# stm32_rf_pio.net
KiCad netlist of a schematic drawn in EAGLE
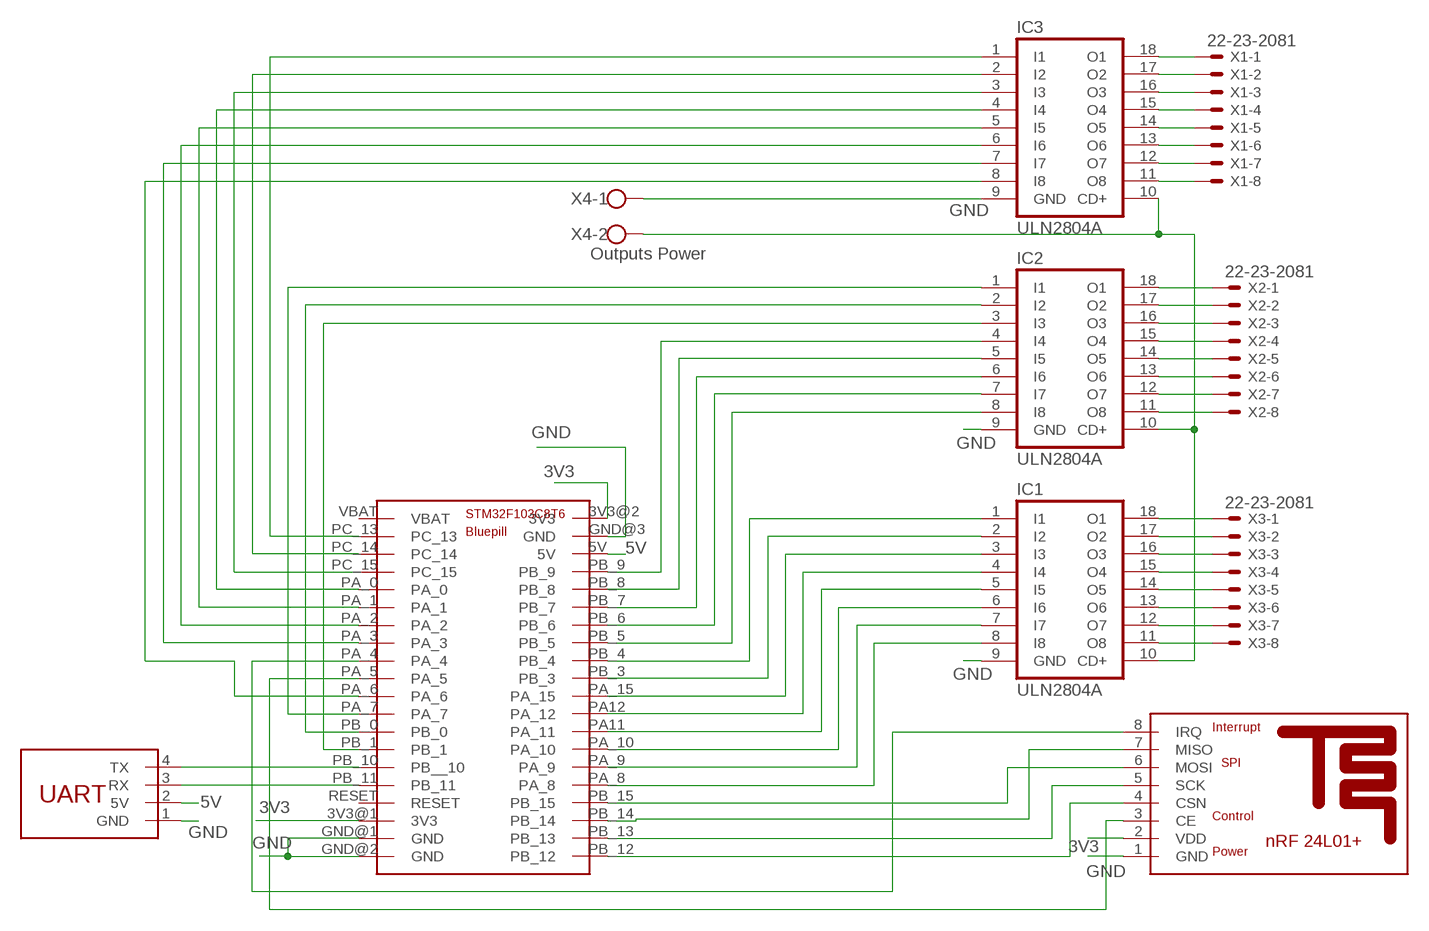
[diagram p0: schematic, sheet 1]

(export (version "E")
  (design (tool "Eeschema 10.0.6"))
  (components
    (comp (ref "IC1")
      (value "ULN2804A")
      (footprint "eagle-import:DIL18")
      (libsource (lib "eagle-import") (part "ULN2804A"))
    )
    (comp (ref "IC2")
      (value "ULN2804A")
      (footprint "eagle-import:DIL18")
      (libsource (lib "eagle-import") (part "ULN2804A"))
    )
    (comp (ref "IC3")
      (value "ULN2804A")
      (footprint "eagle-import:DIL18")
      (libsource (lib "eagle-import") (part "ULN2804A"))
    )
    (comp (ref "U$1")
      (value "STM32_BLUEPILL")
      (footprint "eagle-import:STM32_BLUEPILL")
      (libsource (lib "eagle-import") (part "STM32_BLUEPILL"))
    )
    (comp (ref "U$2")
      (value "NRF24L01+REFDESIGNMINI")
      (footprint "eagle-import:NRF24L01+REFDESIGN-MINI")
      (libsource (lib "eagle-import") (part "NRF24L01+REFDESIGNMINI"))
    )
    (comp (ref "U$3")
      (value "UARTMINI")
      (footprint "eagle-import:UART-MINI")
      (libsource (lib "eagle-import") (part "UARTMINI"))
    )
    (comp (ref "X1")
      (value "22-23-2081")
      (footprint "eagle-import:22-23-2081")
      (fields (field (name "MF") "MOLEX"))
      (libsource (lib "eagle-import") (part "22-23-2081"))
    )
    (comp (ref "X2")
      (value "22-23-2081")
      (footprint "eagle-import:22-23-2081")
      (fields (field (name "MF") "MOLEX"))
      (libsource (lib "eagle-import") (part "22-23-2081"))
    )
    (comp (ref "X3")
      (value "22-23-2081")
      (footprint "eagle-import:22-23-2081")
      (fields (field (name "MF") "MOLEX"))
      (libsource (lib "eagle-import") (part "22-23-2081"))
    )
    (comp (ref "X4")
      (value "Outputs Power")
      (footprint "eagle-import:W237-102")
      (fields (field (name "MPN") "237-102"))
      (libsource (lib "eagle-import") (part "W237-102"))
    )
  )
  (nets
    (net (code "1") (name "/3V3") (class "Default")
      (node (ref "U$1") (pin "3V3@1") (pinfunction "3V3_3V3@1") (pintype "bidirectional"))
      (node (ref "U$1") (pin "3V3@2") (pinfunction "3V3_3V3@2") (pintype "bidirectional"))
      (node (ref "U$2") (pin "2") (pinfunction "VDD_2") (pintype "bidirectional"))
    )
    (net (code "2") (name "/5V") (class "Default")
      (node (ref "U$1") (pin "5V") (pinfunction "5V_5V") (pintype "bidirectional"))
      (node (ref "U$3") (pin "2") (pinfunction "5V_2") (pintype "bidirectional"))
    )
    (net (code "3") (name "/GND") (class "Default")
      (node (ref "IC1") (pin "9") (pinfunction "GND_9") (pintype "power_in"))
      (node (ref "IC2") (pin "9") (pinfunction "GND_9") (pintype "power_in"))
      (node (ref "IC3") (pin "9") (pinfunction "GND_9") (pintype "power_in"))
      (node (ref "U$1") (pin "GND@1") (pinfunction "GND_GND@1") (pintype "bidirectional"))
      (node (ref "U$1") (pin "GND@2") (pinfunction "GND_GND@2") (pintype "bidirectional"))
      (node (ref "U$1") (pin "GND@3") (pinfunction "GND_GND@3") (pintype "bidirectional"))
      (node (ref "U$2") (pin "1") (pinfunction "GND_1") (pintype "bidirectional"))
      (node (ref "U$3") (pin "1") (pinfunction "GND_1") (pintype "bidirectional"))
      (node (ref "X4") (pin "1") (pinfunction "KL_1") (pintype "passive"))
    )
    (net (code "4") (name "Net-(IC1-CD+)") (class "Default")
      (node (ref "IC1") (pin "10") (pinfunction "CD+_10") (pintype "passive"))
      (node (ref "IC2") (pin "10") (pinfunction "CD+_10") (pintype "passive"))
      (node (ref "IC3") (pin "10") (pinfunction "CD+_10") (pintype "passive"))
      (node (ref "X4") (pin "2") (pinfunction "KL_2") (pintype "passive"))
    )
    (net (code "5") (name "Net-(IC1-I1)") (class "Default")
      (node (ref "IC1") (pin "1") (pinfunction "I1_1") (pintype "input"))
      (node (ref "U$1") (pin "PB_4") (pinfunction "PB_4_PB_4") (pintype "bidirectional"))
    )
    (net (code "6") (name "Net-(IC1-I2)") (class "Default")
      (node (ref "IC1") (pin "2") (pinfunction "I2_2") (pintype "input"))
      (node (ref "U$1") (pin "PB_3") (pinfunction "PB_3_PB_3") (pintype "bidirectional"))
    )
    (net (code "7") (name "Net-(IC1-I3)") (class "Default")
      (node (ref "IC1") (pin "3") (pinfunction "I3_3") (pintype "input"))
      (node (ref "U$1") (pin "PA_15") (pinfunction "PA_15_PA_15") (pintype "bidirectional"))
    )
    (net (code "8") (name "Net-(IC1-I4)") (class "Default")
      (node (ref "IC1") (pin "4") (pinfunction "I4_4") (pintype "input"))
      (node (ref "U$1") (pin "PA12") (pinfunction "PA_12_PA12") (pintype "bidirectional"))
    )
    (net (code "9") (name "Net-(IC1-I5)") (class "Default")
      (node (ref "IC1") (pin "5") (pinfunction "I5_5") (pintype "input"))
      (node (ref "U$1") (pin "PA11") (pinfunction "PA_11_PA11") (pintype "bidirectional"))
    )
    (net (code "10") (name "Net-(IC1-I6)") (class "Default")
      (node (ref "IC1") (pin "6") (pinfunction "I6_6") (pintype "input"))
      (node (ref "U$1") (pin "PA_10") (pinfunction "PA_10_PA_10") (pintype "bidirectional"))
    )
    (net (code "11") (name "Net-(IC1-I7)") (class "Default")
      (node (ref "IC1") (pin "7") (pinfunction "I7_7") (pintype "input"))
      (node (ref "U$1") (pin "PA_9") (pinfunction "PA_9_PA_9") (pintype "bidirectional"))
    )
    (net (code "12") (name "Net-(IC1-I8)") (class "Default")
      (node (ref "IC1") (pin "8") (pinfunction "I8_8") (pintype "input"))
      (node (ref "U$1") (pin "PA_8") (pinfunction "PA_8_PA_8") (pintype "bidirectional"))
    )
    (net (code "13") (name "Net-(IC1-O1)") (class "Default")
      (node (ref "IC1") (pin "18") (pinfunction "O1_18") (pintype "open_collector"))
      (node (ref "X3") (pin "1") (pinfunction "S_1") (pintype "passive"))
    )
    (net (code "14") (name "Net-(IC1-O2)") (class "Default")
      (node (ref "IC1") (pin "17") (pinfunction "O2_17") (pintype "open_collector"))
      (node (ref "X3") (pin "2") (pinfunction "S_2") (pintype "passive"))
    )
    (net (code "15") (name "Net-(IC1-O3)") (class "Default")
      (node (ref "IC1") (pin "16") (pinfunction "O3_16") (pintype "open_collector"))
      (node (ref "X3") (pin "3") (pinfunction "S_3") (pintype "passive"))
    )
    (net (code "16") (name "Net-(IC1-O4)") (class "Default")
      (node (ref "IC1") (pin "15") (pinfunction "O4_15") (pintype "open_collector"))
      (node (ref "X3") (pin "4") (pinfunction "S_4") (pintype "passive"))
    )
    (net (code "17") (name "Net-(IC1-O5)") (class "Default")
      (node (ref "IC1") (pin "14") (pinfunction "O5_14") (pintype "open_collector"))
      (node (ref "X3") (pin "5") (pinfunction "S_5") (pintype "passive"))
    )
    (net (code "18") (name "Net-(IC1-O6)") (class "Default")
      (node (ref "IC1") (pin "13") (pinfunction "O6_13") (pintype "open_collector"))
      (node (ref "X3") (pin "6") (pinfunction "S_6") (pintype "passive"))
    )
    (net (code "19") (name "Net-(IC1-O7)") (class "Default")
      (node (ref "IC1") (pin "12") (pinfunction "O7_12") (pintype "open_collector"))
      (node (ref "X3") (pin "7") (pinfunction "S_7") (pintype "passive"))
    )
    (net (code "20") (name "Net-(IC1-O8)") (class "Default")
      (node (ref "IC1") (pin "11") (pinfunction "O8_11") (pintype "open_collector"))
      (node (ref "X3") (pin "8") (pinfunction "S_8") (pintype "passive"))
    )
    (net (code "21") (name "Net-(IC2-I1)") (class "Default")
      (node (ref "IC2") (pin "1") (pinfunction "I1_1") (pintype "input"))
      (node (ref "U$1") (pin "PA_7") (pinfunction "PA_7_PA_7") (pintype "bidirectional"))
    )
    (net (code "22") (name "Net-(IC2-I2)") (class "Default")
      (node (ref "IC2") (pin "2") (pinfunction "I2_2") (pintype "input"))
      (node (ref "U$1") (pin "PB_0") (pinfunction "PB_0_PB_0") (pintype "bidirectional"))
    )
    (net (code "23") (name "Net-(IC2-I3)") (class "Default")
      (node (ref "IC2") (pin "3") (pinfunction "I3_3") (pintype "input"))
      (node (ref "U$1") (pin "PB_1") (pinfunction "PB_1_PB_1") (pintype "bidirectional"))
    )
    (net (code "24") (name "Net-(IC2-I4)") (class "Default")
      (node (ref "IC2") (pin "4") (pinfunction "I4_4") (pintype "input"))
      (node (ref "U$1") (pin "PB_9") (pinfunction "PB_9_PB_9") (pintype "bidirectional"))
    )
    (net (code "25") (name "Net-(IC2-I5)") (class "Default")
      (node (ref "IC2") (pin "5") (pinfunction "I5_5") (pintype "input"))
      (node (ref "U$1") (pin "PB_8") (pinfunction "PB_8_PB_8") (pintype "bidirectional"))
    )
    (net (code "26") (name "Net-(IC2-I6)") (class "Default")
      (node (ref "IC2") (pin "6") (pinfunction "I6_6") (pintype "input"))
      (node (ref "U$1") (pin "PB_7") (pinfunction "PB_7_PB_7") (pintype "bidirectional"))
    )
    (net (code "27") (name "Net-(IC2-I7)") (class "Default")
      (node (ref "IC2") (pin "7") (pinfunction "I7_7") (pintype "input"))
      (node (ref "U$1") (pin "PB_6") (pinfunction "PB_6_PB_6") (pintype "bidirectional"))
    )
    (net (code "28") (name "Net-(IC2-I8)") (class "Default")
      (node (ref "IC2") (pin "8") (pinfunction "I8_8") (pintype "input"))
      (node (ref "U$1") (pin "PB_5") (pinfunction "PB_5_PB_5") (pintype "bidirectional"))
    )
    (net (code "29") (name "Net-(IC2-O1)") (class "Default")
      (node (ref "IC2") (pin "18") (pinfunction "O1_18") (pintype "open_collector"))
      (node (ref "X2") (pin "1") (pinfunction "S_1") (pintype "passive"))
    )
    (net (code "30") (name "Net-(IC2-O2)") (class "Default")
      (node (ref "IC2") (pin "17") (pinfunction "O2_17") (pintype "open_collector"))
      (node (ref "X2") (pin "2") (pinfunction "S_2") (pintype "passive"))
    )
    (net (code "31") (name "Net-(IC2-O3)") (class "Default")
      (node (ref "IC2") (pin "16") (pinfunction "O3_16") (pintype "open_collector"))
      (node (ref "X2") (pin "3") (pinfunction "S_3") (pintype "passive"))
    )
    (net (code "32") (name "Net-(IC2-O4)") (class "Default")
      (node (ref "IC2") (pin "15") (pinfunction "O4_15") (pintype "open_collector"))
      (node (ref "X2") (pin "4") (pinfunction "S_4") (pintype "passive"))
    )
    (net (code "33") (name "Net-(IC2-O5)") (class "Default")
      (node (ref "IC2") (pin "14") (pinfunction "O5_14") (pintype "open_collector"))
      (node (ref "X2") (pin "5") (pinfunction "S_5") (pintype "passive"))
    )
    (net (code "34") (name "Net-(IC2-O6)") (class "Default")
      (node (ref "IC2") (pin "13") (pinfunction "O6_13") (pintype "open_collector"))
      (node (ref "X2") (pin "6") (pinfunction "S_6") (pintype "passive"))
    )
    (net (code "35") (name "Net-(IC2-O7)") (class "Default")
      (node (ref "IC2") (pin "12") (pinfunction "O7_12") (pintype "open_collector"))
      (node (ref "X2") (pin "7") (pinfunction "S_7") (pintype "passive"))
    )
    (net (code "36") (name "Net-(IC2-O8)") (class "Default")
      (node (ref "IC2") (pin "11") (pinfunction "O8_11") (pintype "open_collector"))
      (node (ref "X2") (pin "8") (pinfunction "S_8") (pintype "passive"))
    )
    (net (code "37") (name "Net-(IC3-I1)") (class "Default")
      (node (ref "IC3") (pin "1") (pinfunction "I1_1") (pintype "input"))
      (node (ref "U$1") (pin "PC_13") (pinfunction "PC_13_PC_13") (pintype "bidirectional"))
    )
    (net (code "38") (name "Net-(IC3-I2)") (class "Default")
      (node (ref "IC3") (pin "2") (pinfunction "I2_2") (pintype "input"))
      (node (ref "U$1") (pin "PC_14") (pinfunction "PC_14_PC_14") (pintype "bidirectional"))
    )
    (net (code "39") (name "Net-(IC3-I3)") (class "Default")
      (node (ref "IC3") (pin "3") (pinfunction "I3_3") (pintype "input"))
      (node (ref "U$1") (pin "PC_15") (pinfunction "PC_15_PC_15") (pintype "bidirectional"))
    )
    (net (code "40") (name "Net-(IC3-I4)") (class "Default")
      (node (ref "IC3") (pin "4") (pinfunction "I4_4") (pintype "input"))
      (node (ref "U$1") (pin "PA_0") (pinfunction "PA_0_PA_0") (pintype "bidirectional"))
    )
    (net (code "41") (name "Net-(IC3-I5)") (class "Default")
      (node (ref "IC3") (pin "5") (pinfunction "I5_5") (pintype "input"))
      (node (ref "U$1") (pin "PA_1") (pinfunction "PA_1_PA_1") (pintype "bidirectional"))
    )
    (net (code "42") (name "Net-(IC3-I6)") (class "Default")
      (node (ref "IC3") (pin "6") (pinfunction "I6_6") (pintype "input"))
      (node (ref "U$1") (pin "PA_2") (pinfunction "PA_2_PA_2") (pintype "bidirectional"))
    )
    (net (code "43") (name "Net-(IC3-I7)") (class "Default")
      (node (ref "IC3") (pin "7") (pinfunction "I7_7") (pintype "input"))
      (node (ref "U$1") (pin "PA_3") (pinfunction "PA_3_PA_3") (pintype "bidirectional"))
    )
    (net (code "44") (name "Net-(IC3-I8)") (class "Default")
      (node (ref "IC3") (pin "8") (pinfunction "I8_8") (pintype "input"))
      (node (ref "U$1") (pin "PA_6") (pinfunction "PA_6_PA_6") (pintype "bidirectional"))
    )
    (net (code "45") (name "Net-(IC3-O1)") (class "Default")
      (node (ref "IC3") (pin "18") (pinfunction "O1_18") (pintype "open_collector"))
      (node (ref "X1") (pin "1") (pinfunction "S_1") (pintype "passive"))
    )
    (net (code "46") (name "Net-(IC3-O2)") (class "Default")
      (node (ref "IC3") (pin "17") (pinfunction "O2_17") (pintype "open_collector"))
      (node (ref "X1") (pin "2") (pinfunction "S_2") (pintype "passive"))
    )
    (net (code "47") (name "Net-(IC3-O3)") (class "Default")
      (node (ref "IC3") (pin "16") (pinfunction "O3_16") (pintype "open_collector"))
      (node (ref "X1") (pin "3") (pinfunction "S_3") (pintype "passive"))
    )
    (net (code "48") (name "Net-(IC3-O4)") (class "Default")
      (node (ref "IC3") (pin "15") (pinfunction "O4_15") (pintype "open_collector"))
      (node (ref "X1") (pin "4") (pinfunction "S_4") (pintype "passive"))
    )
    (net (code "49") (name "Net-(IC3-O5)") (class "Default")
      (node (ref "IC3") (pin "14") (pinfunction "O5_14") (pintype "open_collector"))
      (node (ref "X1") (pin "5") (pinfunction "S_5") (pintype "passive"))
    )
    (net (code "50") (name "Net-(IC3-O6)") (class "Default")
      (node (ref "IC3") (pin "13") (pinfunction "O6_13") (pintype "open_collector"))
      (node (ref "X1") (pin "6") (pinfunction "S_6") (pintype "passive"))
    )
    (net (code "51") (name "Net-(IC3-O7)") (class "Default")
      (node (ref "IC3") (pin "12") (pinfunction "O7_12") (pintype "open_collector"))
      (node (ref "X1") (pin "7") (pinfunction "S_7") (pintype "passive"))
    )
    (net (code "52") (name "Net-(IC3-O8)") (class "Default")
      (node (ref "IC3") (pin "11") (pinfunction "O8_11") (pintype "open_collector"))
      (node (ref "X1") (pin "8") (pinfunction "S_8") (pintype "passive"))
    )
    (net (code "53") (name "Net-(U$1-PB__10)") (class "Default")
      (node (ref "U$1") (pin "PB_10") (pinfunction "PB__10_PB_10") (pintype "bidirectional"))
      (node (ref "U$3") (pin "4") (pinfunction "TX_4") (pintype "bidirectional"))
    )
    (net (code "54") (name "Net-(U$2-CE)") (class "Default")
      (node (ref "U$1") (pin "PA_5") (pinfunction "PA_5_PA_5") (pintype "bidirectional"))
      (node (ref "U$2") (pin "3") (pinfunction "CE_3") (pintype "bidirectional"))
    )
    (net (code "55") (name "Net-(U$2-CSN)") (class "Default")
      (node (ref "U$1") (pin "PB_12") (pinfunction "PB_12_PB_12") (pintype "bidirectional"))
      (node (ref "U$2") (pin "4") (pinfunction "CSN_4") (pintype "bidirectional"))
    )
    (net (code "56") (name "Net-(U$2-IRQ)") (class "Default")
      (node (ref "U$1") (pin "PA_4") (pinfunction "PA_4_PA_4") (pintype "bidirectional"))
      (node (ref "U$2") (pin "8") (pinfunction "IRQ_8") (pintype "bidirectional"))
    )
    (net (code "57") (name "Net-(U$2-MISO)") (class "Default")
      (node (ref "U$1") (pin "PB_14") (pinfunction "PB_14_PB_14") (pintype "bidirectional"))
      (node (ref "U$2") (pin "7") (pinfunction "MISO_7") (pintype "bidirectional"))
    )
    (net (code "58") (name "Net-(U$2-MOSI)") (class "Default")
      (node (ref "U$1") (pin "PB_15") (pinfunction "PB_15_PB_15") (pintype "bidirectional"))
      (node (ref "U$2") (pin "6") (pinfunction "MOSI_6") (pintype "bidirectional"))
    )
    (net (code "59") (name "Net-(U$2-SCK)") (class "Default")
      (node (ref "U$1") (pin "PB_13") (pinfunction "PB_13_PB_13") (pintype "bidirectional"))
      (node (ref "U$2") (pin "5") (pinfunction "SCK_5") (pintype "bidirectional"))
    )
    (net (code "60") (name "Net-(U$3-RX)") (class "Default")
      (node (ref "U$1") (pin "PB_11") (pinfunction "PB_11_PB_11") (pintype "bidirectional"))
      (node (ref "U$3") (pin "3") (pinfunction "RX_3") (pintype "bidirectional"))
    )
    (net (code "61") (name "unconnected-(U$1-PadRESET)") (class "Default")
      (node (ref "U$1") (pin "RESET") (pinfunction "RESET_RESET") (pintype "bidirectional"))
    )
    (net (code "62") (name "unconnected-(U$1-PadVBAT)") (class "Default")
      (node (ref "U$1") (pin "VBAT") (pinfunction "VBAT_VBAT") (pintype "bidirectional"))
    )
  )
)
